# MCU.net
KiCad netlist of a schematic drawn in Altium Designer
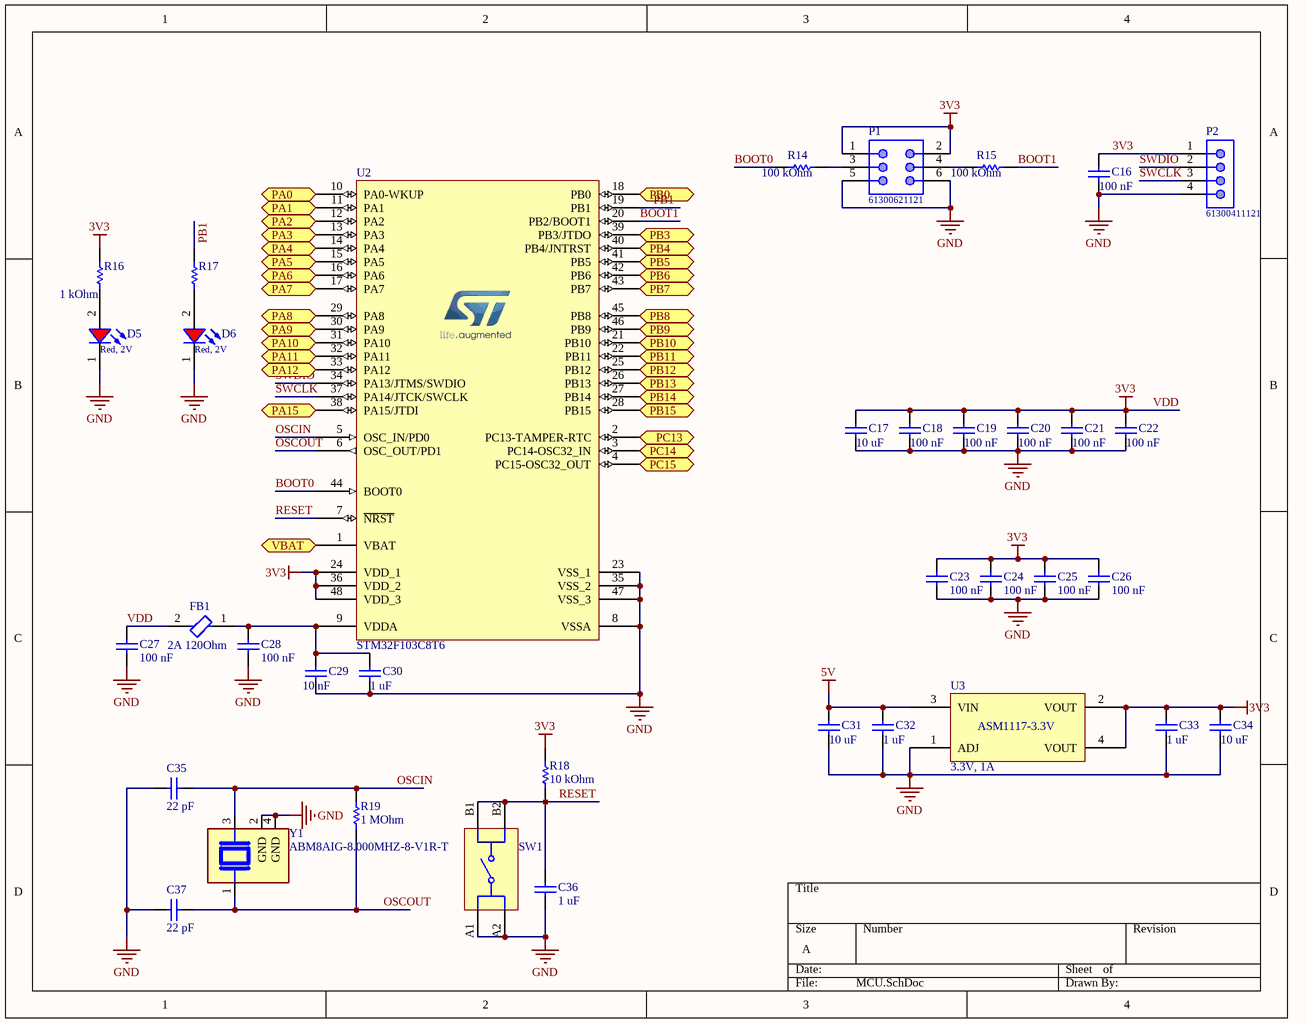
[diagram p0: MCU.SchDoc]

(export (version "E")
  (design (tool "Eeschema 10.0.6"))
  (components
    (comp (ref "C16")
      (value "100 nF")
      (footprint "CAP_0603")
      (description "CAP, size 0603, 100 nF, 50 VDC")
      (fields (field (name "TOLERANCE") "+/-10%"))
      (libsource (lib "Altium_Ceramic_Cap") (part "0106031041050"))
    )
    (comp (ref "C17")
      (value "10 uF")
      (footprint "CAP_0603")
      (description "CAP, size 0603, 10 uF, 10 VDC")
      (fields (field (name "TOLERANCE") "+/-10%"))
      (libsource (lib "Altium_Ceramic_Cap") (part "0106031061010"))
    )
    (comp (ref "C18")
      (value "100 nF")
      (footprint "CAP_0603")
      (description "CAP, size 0603, 100 nF, 50 VDC")
      (fields (field (name "TOLERANCE") "+/-10%"))
      (libsource (lib "Altium_Ceramic_Cap") (part "0106031041050"))
    )
    (comp (ref "C19")
      (value "100 nF")
      (footprint "CAP_0603")
      (description "CAP, size 0603, 100 nF, 50 VDC")
      (fields (field (name "TOLERANCE") "+/-10%"))
      (libsource (lib "Altium_Ceramic_Cap") (part "0106031041050"))
    )
    (comp (ref "C20")
      (value "100 nF")
      (footprint "CAP_0603")
      (description "CAP, size 0603, 100 nF, 50 VDC")
      (fields (field (name "TOLERANCE") "+/-10%"))
      (libsource (lib "Altium_Ceramic_Cap") (part "0106031041050"))
    )
    (comp (ref "C21")
      (value "100 nF")
      (footprint "CAP_0603")
      (description "CAP, size 0603, 100 nF, 50 VDC")
      (fields (field (name "TOLERANCE") "+/-10%"))
      (libsource (lib "Altium_Ceramic_Cap") (part "0106031041050"))
    )
    (comp (ref "C22")
      (value "100 nF")
      (footprint "CAP_0603")
      (description "CAP, size 0603, 100 nF, 50 VDC")
      (fields (field (name "TOLERANCE") "+/-10%"))
      (libsource (lib "Altium_Ceramic_Cap") (part "0106031041050"))
    )
    (comp (ref "C23")
      (value "100 nF")
      (footprint "CAP_0603")
      (description "CAP, size 0603, 100 nF, 50 VDC")
      (fields (field (name "TOLERANCE") "+/-10%"))
      (libsource (lib "Altium_Ceramic_Cap") (part "0106031041050"))
    )
    (comp (ref "C24")
      (value "100 nF")
      (footprint "CAP_0603")
      (description "CAP, size 0603, 100 nF, 50 VDC")
      (fields (field (name "TOLERANCE") "+/-10%"))
      (libsource (lib "Altium_Ceramic_Cap") (part "0106031041050"))
    )
    (comp (ref "C25")
      (value "100 nF")
      (footprint "CAP_0603")
      (description "CAP, size 0603, 100 nF")
      (fields (field (name "TOLERANCE") "+/-10%"))
      (libsource (lib "Altium_Ceramic_Cap") (part "0106031041050"))
    )
    (comp (ref "C26")
      (value "100 nF")
      (footprint "CAP_0603")
      (description "CAP, size 0603, 100 nF, 50 VDC")
      (fields (field (name "TOLERANCE") "+/-10%"))
      (libsource (lib "Altium_Ceramic_Cap") (part "0106031041050"))
    )
    (comp (ref "C27")
      (value "100 nF")
      (footprint "CAP_0603")
      (description "CAP, size 0603, 100 nF, 50 VDC")
      (fields (field (name "TOLERANCE") "+/-10%"))
      (libsource (lib "Altium_Ceramic_Cap") (part "0106031041050"))
    )
    (comp (ref "C28")
      (value "100 nF")
      (footprint "CAP_0603")
      (description "CAP, size 0603, 100 nF, 50 VDC")
      (fields (field (name "TOLERANCE") "+/-10%"))
      (libsource (lib "Altium_Ceramic_Cap") (part "0106031041050"))
    )
    (comp (ref "C29")
      (value "10 nF")
      (footprint "CAP_0603")
      (description "CAP, size 0603, 10 nF, 50 VDC")
      (fields (field (name "TOLERANCE") "+/-5%"))
      (libsource (lib "Altium_Ceramic_Cap") (part "0106031030550"))
    )
    (comp (ref "C30")
      (value "1 uF")
      (footprint "CAP_0603")
      (description "CAP, size 0603, 1 uF, 16 VDC")
      (fields (field (name "TOLERANCE") "+/-10%"))
      (libsource (lib "Altium_Ceramic_Cap") (part "0106031051016"))
    )
    (comp (ref "C31")
      (value "10 uF")
      (footprint "CAP_0603")
      (description "CAP, size 0603, 10 uF, 10 VDC")
      (fields (field (name "TOLERANCE") "+/-10%"))
      (libsource (lib "Altium_Ceramic_Cap") (part "0106031061010"))
    )
    (comp (ref "C32")
      (value "1 uF")
      (footprint "CAP_0603")
      (description "CAP, size 0603, 1 uF, 16 VDC")
      (fields (field (name "TOLERANCE") "+/-10%"))
      (libsource (lib "Altium_Ceramic_Cap") (part "0106031051016"))
    )
    (comp (ref "C33")
      (value "1 uF")
      (footprint "CAP_0603")
      (description "CAP, size 0603, 1 uF, 16 VDC")
      (fields (field (name "TOLERANCE") "+/-10%"))
      (libsource (lib "Altium_Ceramic_Cap") (part "0106031051016"))
    )
    (comp (ref "C34")
      (value "10 uF")
      (footprint "CAP_0603")
      (description "CAP, size 0603, 10 uF, 10 VDC")
      (fields (field (name "TOLERANCE") "+/-10%"))
      (libsource (lib "Altium_Ceramic_Cap") (part "0106031061010"))
    )
    (comp (ref "C35")
      (value "22 pF")
      (footprint "CAP_0603")
      (description "CAP, size 0603, 22 pF, 50 VDC")
      (fields (field (name "TOLERANCE") "+/-5%"))
      (libsource (lib "Altium_Ceramic_Cap") (part "0106032200550"))
    )
    (comp (ref "C36")
      (value "1 uF")
      (footprint "CAP_0603")
      (description "CAP, size 0603, 1 uF, 35 VDC")
      (fields (field (name "TOLERANCE") "+/-10%"))
      (libsource (lib "Altium_Ceramic_Cap") (part "0106031051035"))
    )
    (comp (ref "C37")
      (value "22 pF")
      (footprint "CAP_0603")
      (description "CAP, size 0603, 22 pF, 50 VDC")
      (fields (field (name "TOLERANCE") "+/-5%"))
      (libsource (lib "Altium_Ceramic_Cap") (part "0106032200550"))
    )
    (comp (ref "D5")
      (value "Red, 2V")
      (footprint "WL-SMCW_0603_H=0.7mm")
      (description "WL-SMCW SMT Mono-color Chip LED Waterclear, size 0603, Red, 2V, 140deg")
      (libsource (lib "Altium_LED") (part "160603RedClear"))
    )
    (comp (ref "D6")
      (value "Red, 2V")
      (footprint "WL-SMCW_0603_H=0.7mm")
      (description "WL-SMCW SMT Mono-color Chip LED Waterclear, size 0603, Red, 2V, 140deg")
      (libsource (lib "Altium_LED") (part "160603RedClear"))
    )
    (comp (ref "FB1")
      (value "2A 120Ohm")
      (footprint "FP-BLM21-0_2-t0_85-e0_5-IPC_A")
      (description "FERRITE BEAD 120 OHM 0805 1LN")
      (fields (field (name "TOLERANCE") "25%"))
      (libsource (lib "Altium Content Vault") (part "5f30dd21d616792df468990f7003faa"))
    )
    (comp (ref "P1")
      (value "61300621121")
      (footprint "61300621121")
      (description "WR-PHD Pin Header, THT, pitch 2.54mm, Dual Row, Vertical, 6p")
      (fields (field (name "MANUFACTURER") "Wurth Elektronik"))
      (libsource (lib "Altium_Header") (part "61300621121"))
    )
    (comp (ref "P2")
      (value "61300411121")
      (footprint "61300411121")
      (description "WR-PHD Pin Header, THT, pitch 2.54mm, Single Row, Vertical, 4p")
      (fields (field (name "MANUFACTURER") "Wurth Elektronik"))
      (libsource (lib "Altium_Header") (part "61300411121"))
    )
    (comp (ref "R14")
      (value "100 kOhm")
      (footprint "resistor_0603")
      (description "RES, size 0603, 100 KOhm, 1/4 W")
      (libsource (lib "Altium_Resistor") (part "0006031041"))
    )
    (comp (ref "R15")
      (value "100 kOhm")
      (footprint "resistor_0603")
      (description "RES, size 0603, 100 KOhm, 1/4 W")
      (libsource (lib "Altium_Resistor") (part "0006031041"))
    )
    (comp (ref "R16")
      (value "1 kOhm")
      (footprint "resistor_0603")
      (description "RES, size 0603, 1 KOhm, 1/4 W")
      (libsource (lib "Altium_Resistor") (part "0006031021"))
    )
    (comp (ref "R17")
      (value "1 kOhm")
      (footprint "resistor_0603")
      (description "RES, size 0603, 1 KOhm, 1/4 W")
      (libsource (lib "Altium_Resistor") (part "0006031021"))
    )
    (comp (ref "R18")
      (value "10 kOhm")
      (footprint "resistor_0603")
      (description "RES, size 0603, 10 KOhm, 1/4 W")
      (libsource (lib "Altium_Resistor") (part "0006031031"))
    )
    (comp (ref "R19")
      (value "1 MOhm")
      (footprint "resistor_0603")
      (description "RES, size 0603, 1 MOhm, 1/4 W")
      (libsource (lib "Altium_Resistor") (part "0006031055"))
    )
    (comp (ref "SW1")
      (value "430152043826")
      (footprint "WS-TASV_L6W6H4.3_4301x20438x6")
      (description "WS-TASV SMT Tact Switch, L6 x W6 x H4.3mm, 260g, SPST-NO, 12V, 50mA")
      (fields (field (name "MANUFACTURER") "Wurth Elektronik"))
      (libsource (lib "Altium_Button") (part "430152043826"))
    )
    (comp (ref "U2")
      (value "STM32F103C8T6")
      (footprint "STM32F103C8T6")
      (description "ARM Microcontrollers - MCU 32BIT Cortex M3 64KB 20KB RAM 2X12 ADC")
      (fields (field (name "MANUFACTURER") "STM"))
      (libsource (lib "Altium_MCU") (part "STM32F103C8T6"))
    )
    (comp (ref "U3")
      (value "3.3V, 1A")
      (footprint "AMS1117-3.3V SOT223")
      (description "AMS1117-3.3V, OUT 3.3V 1A.")
      (fields (field (name "MANUFACTURER") "AMS"))
      (libsource (lib "Altium_Power_Supply_IC") (part "AMS1117-3.3V"))
    )
    (comp (ref "Y1")
      (value "ABM8AIG-8.000MHZ-8-V1R-T")
      (footprint "XTAL_ABM8AIG-8.000MHZ-8-V1R-T")
      (description "8 MHz Â±10ppm Crystal 8pF 500 Ohms 4-SMD, No Lead")
      (fields (field (name "MF") "Abracon LLC"))
      (libsource (lib "ABM8AIG-8.000MHZ-8-V1R-T (1)") (part "ABM8AIG-8.000MHZ-8-V1R-T"))
    )
  )
  (nets
    (net (code "1") (name "/BOOT0") (class "Default")
      (node (ref "R14") (pin "1") (pinfunction "1_1") (pintype "passive"))
      (node (ref "U2") (pin "44") (pinfunction "BOOT0_44") (pintype "input"))
    )
    (net (code "2") (name "/BOOT1") (class "Default")
      (node (ref "R15") (pin "2") (pinfunction "2_2") (pintype "passive"))
      (node (ref "U2") (pin "20") (pinfunction "PB2/BOOT1_20") (pintype "bidirectional"))
    )
    (net (code "3") (name "/OSCIN") (class "Default")
      (node (ref "C35") (pin "1") (pinfunction "1_1") (pintype "passive"))
      (node (ref "R19") (pin "2") (pinfunction "2_2") (pintype "passive"))
      (node (ref "U2") (pin "5") (pinfunction "OSC_IN/PD0_5") (pintype "input"))
      (node (ref "Y1") (pin "3") (pinfunction "2_3") (pintype "passive"))
    )
    (net (code "4") (name "/OSCOUT") (class "Default")
      (node (ref "C37") (pin "1") (pinfunction "1_1") (pintype "passive"))
      (node (ref "R19") (pin "1") (pinfunction "1_1") (pintype "passive"))
      (node (ref "U2") (pin "6") (pinfunction "OSC_OUT/PD1_6") (pintype "output"))
      (node (ref "Y1") (pin "1") (pinfunction "1_1") (pintype "passive"))
    )
    (net (code "5") (name "/PA0") (class "Default")
      (node (ref "U2") (pin "10") (pinfunction "PA0-WKUP_10") (pintype "bidirectional"))
    )
    (net (code "6") (name "/PA1") (class "Default")
      (node (ref "U2") (pin "11") (pinfunction "PA1_11") (pintype "bidirectional"))
    )
    (net (code "7") (name "/PA2") (class "Default")
      (node (ref "U2") (pin "12") (pinfunction "PA2_12") (pintype "bidirectional"))
    )
    (net (code "8") (name "/PA3") (class "Default")
      (node (ref "U2") (pin "13") (pinfunction "PA3_13") (pintype "bidirectional"))
    )
    (net (code "9") (name "/PA4") (class "Default")
      (node (ref "U2") (pin "14") (pinfunction "PA4_14") (pintype "bidirectional"))
    )
    (net (code "10") (name "/PA5") (class "Default")
      (node (ref "U2") (pin "15") (pinfunction "PA5_15") (pintype "bidirectional"))
    )
    (net (code "11") (name "/PA6") (class "Default")
      (node (ref "U2") (pin "16") (pinfunction "PA6_16") (pintype "bidirectional"))
    )
    (net (code "12") (name "/PA7") (class "Default")
      (node (ref "U2") (pin "17") (pinfunction "PA7_17") (pintype "bidirectional"))
    )
    (net (code "13") (name "/PA8") (class "Default")
      (node (ref "U2") (pin "29") (pinfunction "PA8_29") (pintype "bidirectional"))
    )
    (net (code "14") (name "/PA9") (class "Default")
      (node (ref "U2") (pin "30") (pinfunction "PA9_30") (pintype "bidirectional"))
    )
    (net (code "15") (name "/PA10") (class "Default")
      (node (ref "U2") (pin "31") (pinfunction "PA10_31") (pintype "bidirectional"))
    )
    (net (code "16") (name "/PA11") (class "Default")
      (node (ref "U2") (pin "32") (pinfunction "PA11_32") (pintype "bidirectional"))
    )
    (net (code "17") (name "/PA12") (class "Default")
      (node (ref "U2") (pin "33") (pinfunction "PA12_33") (pintype "bidirectional"))
    )
    (net (code "18") (name "/PA15") (class "Default")
      (node (ref "U2") (pin "38") (pinfunction "PA15/JTDI_38") (pintype "bidirectional"))
    )
    (net (code "19") (name "/PB0") (class "Default")
      (node (ref "U2") (pin "18") (pinfunction "PB0_18") (pintype "bidirectional"))
    )
    (net (code "20") (name "/PB1") (class "Default")
      (node (ref "R17") (pin "2") (pinfunction "2_2") (pintype "passive"))
      (node (ref "U2") (pin "19") (pinfunction "PB1_19") (pintype "bidirectional"))
    )
    (net (code "21") (name "/PB3") (class "Default")
      (node (ref "U2") (pin "39") (pinfunction "PB3/JTDO_39") (pintype "bidirectional"))
    )
    (net (code "22") (name "/PB4") (class "Default")
      (node (ref "U2") (pin "40") (pinfunction "PB4/JNTRST_40") (pintype "bidirectional"))
    )
    (net (code "23") (name "/PB5") (class "Default")
      (node (ref "U2") (pin "41") (pinfunction "PB5_41") (pintype "bidirectional"))
    )
    (net (code "24") (name "/PB6") (class "Default")
      (node (ref "U2") (pin "42") (pinfunction "PB6_42") (pintype "bidirectional"))
    )
    (net (code "25") (name "/PB7") (class "Default")
      (node (ref "U2") (pin "43") (pinfunction "PB7_43") (pintype "bidirectional"))
    )
    (net (code "26") (name "/PB8") (class "Default")
      (node (ref "U2") (pin "45") (pinfunction "PB8_45") (pintype "bidirectional"))
    )
    (net (code "27") (name "/PB9") (class "Default")
      (node (ref "U2") (pin "46") (pinfunction "PB9_46") (pintype "bidirectional"))
    )
    (net (code "28") (name "/PB10") (class "Default")
      (node (ref "U2") (pin "21") (pinfunction "PB10_21") (pintype "bidirectional"))
    )
    (net (code "29") (name "/PB11") (class "Default")
      (node (ref "U2") (pin "22") (pinfunction "PB11_22") (pintype "bidirectional"))
    )
    (net (code "30") (name "/PB12") (class "Default")
      (node (ref "U2") (pin "25") (pinfunction "PB12_25") (pintype "bidirectional"))
    )
    (net (code "31") (name "/PB13") (class "Default")
      (node (ref "U2") (pin "26") (pinfunction "PB13_26") (pintype "bidirectional"))
    )
    (net (code "32") (name "/PB14") (class "Default")
      (node (ref "U2") (pin "27") (pinfunction "PB14_27") (pintype "bidirectional"))
    )
    (net (code "33") (name "/PB15") (class "Default")
      (node (ref "U2") (pin "28") (pinfunction "PB15_28") (pintype "bidirectional"))
    )
    (net (code "34") (name "/PC13") (class "Default")
      (node (ref "U2") (pin "2") (pinfunction "PC13-TAMPER-RTC_2") (pintype "bidirectional"))
    )
    (net (code "35") (name "/PC14") (class "Default")
      (node (ref "U2") (pin "3") (pinfunction "PC14-OSC32_IN_3") (pintype "bidirectional"))
    )
    (net (code "36") (name "/PC15") (class "Default")
      (node (ref "U2") (pin "4") (pinfunction "PC15-OSC32_OUT_4") (pintype "bidirectional"))
    )
    (net (code "37") (name "/RESET") (class "Default")
      (node (ref "C36") (pin "2") (pinfunction "2_2") (pintype "passive"))
      (node (ref "R18") (pin "1") (pinfunction "1_1") (pintype "passive"))
      (node (ref "SW1") (pin "B1") (pinfunction "B1_B1") (pintype "passive"))
      (node (ref "SW1") (pin "B2") (pinfunction "B2_B2") (pintype "passive"))
      (node (ref "U2") (pin "7") (pinfunction "~{NRST}_7") (pintype "bidirectional"))
    )
    (net (code "38") (name "/SWCLK") (class "Default")
      (node (ref "P2") (pin "3") (pinfunction "3_3") (pintype "passive"))
      (node (ref "U2") (pin "37") (pinfunction "PA14/JTCK/SWCLK_37") (pintype "bidirectional"))
    )
    (net (code "39") (name "/SWDIO") (class "Default")
      (node (ref "P2") (pin "2") (pinfunction "2_2") (pintype "passive"))
      (node (ref "U2") (pin "34") (pinfunction "PA13/JTMS/SWDIO_34") (pintype "bidirectional"))
    )
    (net (code "40") (name "/VBAT") (class "Default")
      (node (ref "U2") (pin "1") (pinfunction "VBAT_1") (pintype "power_in"))
    )
    (net (code "41") (name "3V3") (class "Default")
      (node (ref "C16") (pin "2") (pinfunction "2_2") (pintype "passive"))
      (node (ref "C17") (pin "2") (pinfunction "2_2") (pintype "passive"))
      (node (ref "C18") (pin "2") (pinfunction "2_2") (pintype "passive"))
      (node (ref "C19") (pin "2") (pinfunction "2_2") (pintype "passive"))
      (node (ref "C20") (pin "2") (pinfunction "2_2") (pintype "passive"))
      (node (ref "C21") (pin "2") (pinfunction "2_2") (pintype "passive"))
      (node (ref "C22") (pin "2") (pinfunction "2_2") (pintype "passive"))
      (node (ref "C23") (pin "2") (pinfunction "2_2") (pintype "passive"))
      (node (ref "C24") (pin "2") (pinfunction "2_2") (pintype "passive"))
      (node (ref "C25") (pin "2") (pinfunction "2_2") (pintype "passive"))
      (node (ref "C26") (pin "2") (pinfunction "2_2") (pintype "passive"))
      (node (ref "C27") (pin "2") (pinfunction "2_2") (pintype "passive"))
      (node (ref "C33") (pin "2") (pinfunction "2_2") (pintype "passive"))
      (node (ref "C34") (pin "2") (pinfunction "2_2") (pintype "passive"))
      (node (ref "FB1") (pin "2") (pinfunction "2_2") (pintype "passive"))
      (node (ref "P1") (pin "1") (pinfunction "1_1") (pintype "passive"))
      (node (ref "P1") (pin "2") (pinfunction "2_2") (pintype "passive"))
      (node (ref "P2") (pin "1") (pinfunction "1_1") (pintype "passive"))
      (node (ref "R16") (pin "2") (pinfunction "2_2") (pintype "passive"))
      (node (ref "R18") (pin "2") (pinfunction "2_2") (pintype "passive"))
      (node (ref "U2") (pin "24") (pinfunction "VDD_1_24") (pintype "power_in"))
      (node (ref "U2") (pin "36") (pinfunction "VDD_2_36") (pintype "power_in"))
      (node (ref "U2") (pin "48") (pinfunction "VDD_3_48") (pintype "power_in"))
      (node (ref "U3") (pin "2") (pinfunction "VOUT_2") (pintype "passive"))
      (node (ref "U3") (pin "4") (pinfunction "VOUT_4") (pintype "power_in"))
    )
    (net (code "42") (name "5V") (class "Default")
      (node (ref "C31") (pin "2") (pinfunction "2_2") (pintype "passive"))
      (node (ref "C32") (pin "2") (pinfunction "2_2") (pintype "passive"))
      (node (ref "U3") (pin "3") (pinfunction "VIN_3") (pintype "passive"))
    )
    (net (code "43") (name "GND") (class "Default")
      (node (ref "C16") (pin "1") (pinfunction "1_1") (pintype "passive"))
      (node (ref "C17") (pin "1") (pinfunction "1_1") (pintype "passive"))
      (node (ref "C18") (pin "1") (pinfunction "1_1") (pintype "passive"))
      (node (ref "C19") (pin "1") (pinfunction "1_1") (pintype "passive"))
      (node (ref "C20") (pin "1") (pinfunction "1_1") (pintype "passive"))
      (node (ref "C21") (pin "1") (pinfunction "1_1") (pintype "passive"))
      (node (ref "C22") (pin "1") (pinfunction "1_1") (pintype "passive"))
      (node (ref "C23") (pin "1") (pinfunction "1_1") (pintype "passive"))
      (node (ref "C24") (pin "1") (pinfunction "1_1") (pintype "passive"))
      (node (ref "C25") (pin "1") (pinfunction "1_1") (pintype "passive"))
      (node (ref "C26") (pin "1") (pinfunction "1_1") (pintype "passive"))
      (node (ref "C27") (pin "1") (pinfunction "1_1") (pintype "passive"))
      (node (ref "C28") (pin "1") (pinfunction "1_1") (pintype "passive"))
      (node (ref "C29") (pin "1") (pinfunction "1_1") (pintype "passive"))
      (node (ref "C30") (pin "1") (pinfunction "1_1") (pintype "passive"))
      (node (ref "C31") (pin "1") (pinfunction "1_1") (pintype "passive"))
      (node (ref "C32") (pin "1") (pinfunction "1_1") (pintype "passive"))
      (node (ref "C33") (pin "1") (pinfunction "1_1") (pintype "passive"))
      (node (ref "C34") (pin "1") (pinfunction "1_1") (pintype "passive"))
      (node (ref "C35") (pin "2") (pinfunction "2_2") (pintype "passive"))
      (node (ref "C36") (pin "1") (pinfunction "1_1") (pintype "passive"))
      (node (ref "C37") (pin "2") (pinfunction "2_2") (pintype "passive"))
      (node (ref "D5") (pin "1") (pinfunction "K_1") (pintype "passive"))
      (node (ref "D6") (pin "1") (pinfunction "K_1") (pintype "passive"))
      (node (ref "P1") (pin "5") (pinfunction "5_5") (pintype "passive"))
      (node (ref "P1") (pin "6") (pinfunction "6_6") (pintype "passive"))
      (node (ref "P2") (pin "4") (pinfunction "4_4") (pintype "passive"))
      (node (ref "SW1") (pin "A1") (pinfunction "A1_A1") (pintype "passive"))
      (node (ref "SW1") (pin "A2") (pinfunction "A2_A2") (pintype "passive"))
      (node (ref "U2") (pin "23") (pinfunction "VSS_1_23") (pintype "power_in"))
      (node (ref "U2") (pin "35") (pinfunction "VSS_2_35") (pintype "power_in"))
      (node (ref "U2") (pin "47") (pinfunction "VSS_3_47") (pintype "power_in"))
      (node (ref "U2") (pin "8") (pinfunction "VSSA_8") (pintype "power_in"))
      (node (ref "U3") (pin "1") (pinfunction "ADJ_1") (pintype "power_in"))
      (node (ref "Y1") (pin "2") (pinfunction "GND_2") (pintype "power_in"))
      (node (ref "Y1") (pin "4") (pinfunction "GND_4") (pintype "power_in"))
    )
    (net (code "44") (name "Net-(D5-A)") (class "Default")
      (node (ref "D5") (pin "2") (pinfunction "A_2") (pintype "passive"))
      (node (ref "R16") (pin "1") (pinfunction "1_1") (pintype "passive"))
    )
    (net (code "45") (name "Net-(D6-A)") (class "Default")
      (node (ref "D6") (pin "2") (pinfunction "A_2") (pintype "passive"))
      (node (ref "R17") (pin "1") (pinfunction "1_1") (pintype "passive"))
    )
    (net (code "46") (name "Net-(P1-Pad3)") (class "Default")
      (node (ref "P1") (pin "3") (pinfunction "3_3") (pintype "passive"))
      (node (ref "R14") (pin "2") (pinfunction "2_2") (pintype "passive"))
    )
    (net (code "47") (name "Net-(P1-Pad4)") (class "Default")
      (node (ref "P1") (pin "4") (pinfunction "4_4") (pintype "passive"))
      (node (ref "R15") (pin "1") (pinfunction "1_1") (pintype "passive"))
    )
    (net (code "48") (name "Net-(U2-VDDA)") (class "Default")
      (node (ref "C28") (pin "2") (pinfunction "2_2") (pintype "passive"))
      (node (ref "C29") (pin "2") (pinfunction "2_2") (pintype "passive"))
      (node (ref "C30") (pin "2") (pinfunction "2_2") (pintype "passive"))
      (node (ref "FB1") (pin "1") (pinfunction "1_1") (pintype "passive"))
      (node (ref "U2") (pin "9") (pinfunction "VDDA_9") (pintype "power_in"))
    )
  )
)
